# Half_Bridge_Driver.net
KiCad netlist of a schematic drawn in Altium Designer
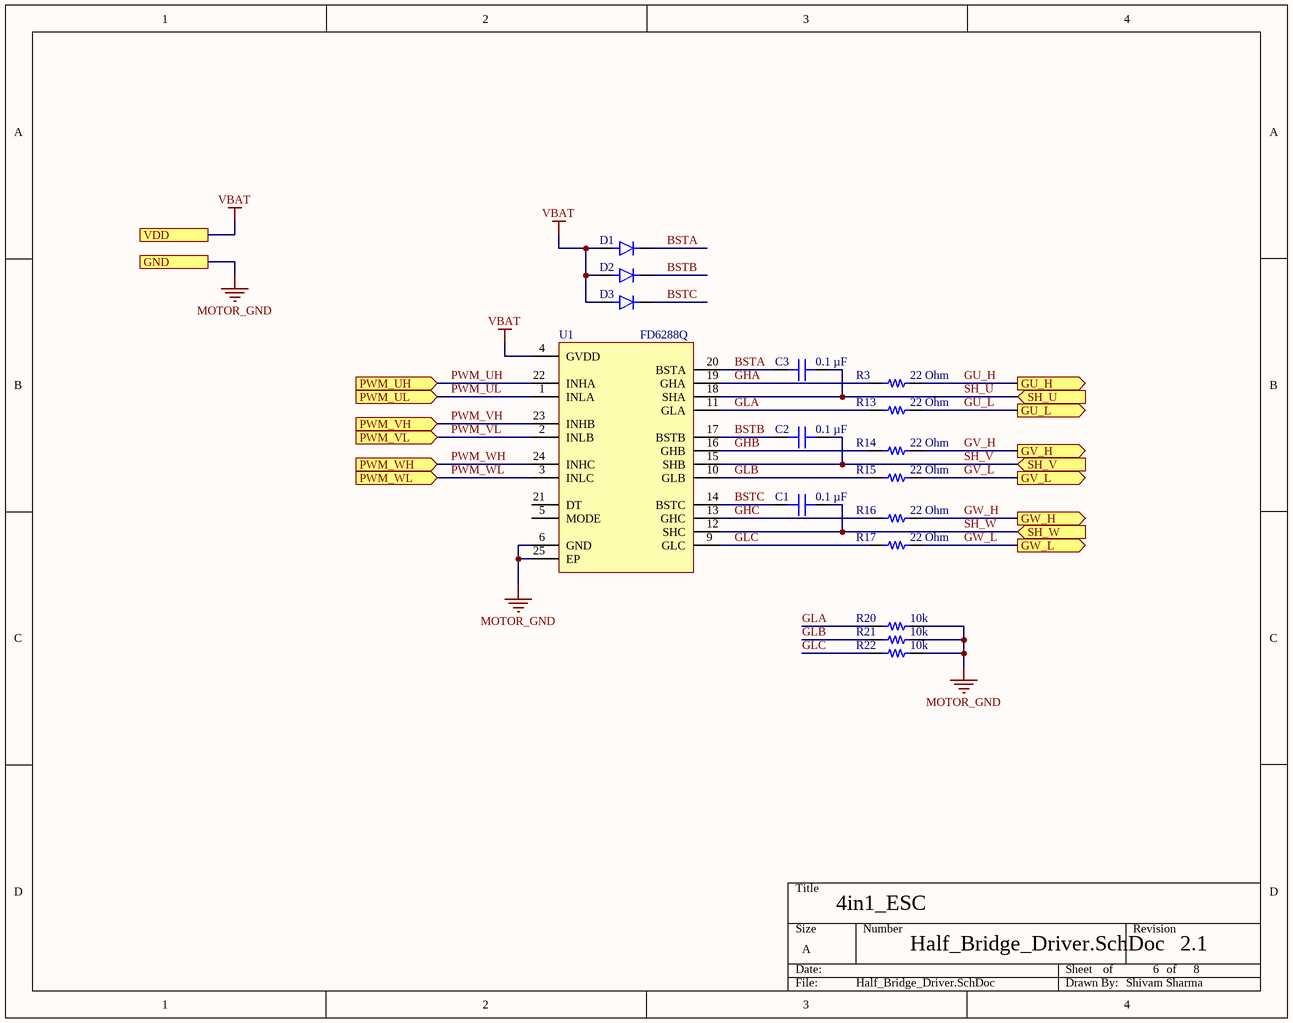
[diagram p0: Half_Bridge_Driver.SchDoc]

(export (version "E")
  (design (tool "Eeschema 10.0.6"))
  (components
    (comp (ref "C1")
      (value "0.1 µF")
      (footprint "CAP 0201_0603")
      (description "CAP CER 0.1UF 35V X5R 0201")
      (fields
        (field (name "PART NUMBER") "GRT033R6YA104KE01D")
        (field (name "MANUFACTURER") "Murata Electronics")
      )
      (libsource (lib "Celestial Altium Library - altium_library") (part "Capacitor"))
    )
    (comp (ref "C2")
      (value "0.1 µF")
      (footprint "CAP 0201_0603")
      (description "CAP CER 0.1UF 35V X5R 0201")
      (fields
        (field (name "PART NUMBER") "GRT033R6YA104KE01D")
        (field (name "MANUFACTURER") "Murata Electronics")
      )
      (libsource (lib "Celestial Altium Library - altium_library") (part "Capacitor"))
    )
    (comp (ref "C3")
      (value "0.1 µF")
      (footprint "CAP 0201_0603")
      (description "CAP CER 0.1UF 35V X5R 0201")
      (fields
        (field (name "PART NUMBER") "GRT033R6YA104KE01D")
        (field (name "MANUFACTURER") "Murata Electronics")
      )
      (libsource (lib "Celestial Altium Library - altium_library") (part "Capacitor"))
    )
    (comp (ref "D1")
      (value "Diode")
      (footprint "Diode DFN1608D-2 (SOD1608)")
      (description "DFN1608D-2 (SOD1608)")
      (fields (field (name "MANUFACTURER") "Cree") (field (name "MOUSER PART NUMBER") "941-CLV1LFKBC7673673"))
      (libsource (lib "IC") (part "Diode"))
    )
    (comp (ref "D2")
      (value "Diode")
      (footprint "Diode DFN1608D-2 (SOD1608)")
      (description "DFN1608D-2 (SOD1608)")
      (fields (field (name "MANUFACTURER") "Cree") (field (name "MOUSER PART NUMBER") "941-CLV1LFKBC7673673"))
      (libsource (lib "IC") (part "Diode"))
    )
    (comp (ref "D3")
      (value "Diode")
      (footprint "Diode DFN1608D-2 (SOD1608)")
      (description "DFN1608D-2 (SOD1608)")
      (fields (field (name "MANUFACTURER") "Cree") (field (name "MOUSER PART NUMBER") "941-CLV1LFKBC7673673"))
      (libsource (lib "IC") (part "Diode"))
    )
    (comp (ref "R3")
      (value "22 Ohm")
      (footprint "RES 0402_1005")
      (description "RES 14.3K OHM 1% 1/10W 0402")
      (fields
        (field (name "PART NUMBER") "RK73H1ETTP1432F")
        (field (name "MANUFACTURER") "KOA Speer Electronics, Inc.")
      )
      (libsource (lib "Celestial Altium Library - altium_library") (part "Resistor"))
    )
    (comp (ref "R13")
      (value "22 Ohm")
      (footprint "RES 0402_1005")
      (description "RES 14.3K OHM 1% 1/10W 0402")
      (fields
        (field (name "PART NUMBER") "RK73H1ETTP1432F")
        (field (name "MANUFACTURER") "KOA Speer Electronics, Inc.")
      )
      (libsource (lib "Celestial Altium Library - altium_library") (part "Resistor"))
    )
    (comp (ref "R14")
      (value "22 Ohm")
      (footprint "RES 0402_1005")
      (description "RES 14.3K OHM 1% 1/10W 0402")
      (fields
        (field (name "PART NUMBER") "RK73H1ETTP1432F")
        (field (name "MANUFACTURER") "KOA Speer Electronics, Inc.")
      )
      (libsource (lib "Celestial Altium Library - altium_library") (part "Resistor"))
    )
    (comp (ref "R15")
      (value "22 Ohm")
      (footprint "RES 0402_1005")
      (description "RES 14.3K OHM 1% 1/10W 0402")
      (fields
        (field (name "PART NUMBER") "RK73H1ETTP1432F")
        (field (name "MANUFACTURER") "KOA Speer Electronics, Inc.")
      )
      (libsource (lib "Celestial Altium Library - altium_library") (part "Resistor"))
    )
    (comp (ref "R16")
      (value "22 Ohm")
      (footprint "RES 0402_1005")
      (description "RES 14.3K OHM 1% 1/10W 0402")
      (fields
        (field (name "PART NUMBER") "RK73H1ETTP1432F")
        (field (name "MANUFACTURER") "KOA Speer Electronics, Inc.")
      )
      (libsource (lib "Celestial Altium Library - altium_library") (part "Resistor"))
    )
    (comp (ref "R17")
      (value "22 Ohm")
      (footprint "RES 0402_1005")
      (description "RES 14.3K OHM 1% 1/10W 0402")
      (fields
        (field (name "PART NUMBER") "RK73H1ETTP1432F")
        (field (name "MANUFACTURER") "KOA Speer Electronics, Inc.")
      )
      (libsource (lib "Celestial Altium Library - altium_library") (part "Resistor"))
    )
    (comp (ref "R20")
      (value "10k")
      (footprint "RES 0201_0603")
      (description "RES SMD 10K OHM 1% 1/20W 0201")
      (fields (field (name "PART NUMBER") "CRCW020110K0FKED") (field (name "MANUFACTURER") "Vishay Dale"))
      (libsource (lib "Celestial Altium Library - altium_library") (part "Resistor"))
    )
    (comp (ref "R21")
      (value "10k")
      (footprint "RES 0201_0603")
      (description "RES SMD 10K OHM 1% 1/20W 0201")
      (fields (field (name "PART NUMBER") "CRCW020110K0FKED") (field (name "MANUFACTURER") "Vishay Dale"))
      (libsource (lib "Celestial Altium Library - altium_library") (part "Resistor"))
    )
    (comp (ref "R22")
      (value "10k")
      (footprint "RES 0201_0603")
      (description "RES SMD 10K OHM 1% 1/20W 0201")
      (fields (field (name "PART NUMBER") "CRCW020110K0FKED") (field (name "MANUFACTURER") "Vishay Dale"))
      (libsource (lib "Celestial Altium Library - altium_library") (part "Resistor"))
    )
    (comp (ref "U1")
      (value "FD6288Q")
      (footprint "QFN50P400X400X100-25N")
      (description "3 Phase Gate Driver 1.5-2.2A")
      (fields (field (name "MF") "Texas Instruments") (field (name "MP") "UCC27282DRCR"))
      (libsource (lib "IC") (part "FD6288Q"))
    )
  )
  (nets
    (net (code "1") (name "/BSTA") (class "Default")
      (node (ref "C3") (pin "1") (pinfunction "1_1") (pintype "passive"))
      (node (ref "D1") (pin "1") (pinfunction "A_1") (pintype "passive"))
      (node (ref "U1") (pin "20") (pinfunction "BSTA_20") (pintype "passive"))
    )
    (net (code "2") (name "/BSTB") (class "Default")
      (node (ref "C2") (pin "1") (pinfunction "1_1") (pintype "passive"))
      (node (ref "D2") (pin "1") (pinfunction "A_1") (pintype "passive"))
      (node (ref "U1") (pin "17") (pinfunction "BSTB_17") (pintype "passive"))
    )
    (net (code "3") (name "/BSTC") (class "Default")
      (node (ref "C1") (pin "1") (pinfunction "1_1") (pintype "passive"))
      (node (ref "D3") (pin "1") (pinfunction "A_1") (pintype "passive"))
      (node (ref "U1") (pin "14") (pinfunction "BSTC_14") (pintype "passive"))
    )
    (net (code "4") (name "/GHA") (class "Default")
      (node (ref "R3") (pin "1") (pinfunction "1_1") (pintype "passive"))
      (node (ref "U1") (pin "19") (pinfunction "GHA_19") (pintype "passive"))
    )
    (net (code "5") (name "/GHB") (class "Default")
      (node (ref "R14") (pin "1") (pinfunction "1_1") (pintype "passive"))
      (node (ref "U1") (pin "16") (pinfunction "GHB_16") (pintype "passive"))
    )
    (net (code "6") (name "/GHC") (class "Default")
      (node (ref "R16") (pin "1") (pinfunction "1_1") (pintype "passive"))
      (node (ref "U1") (pin "13") (pinfunction "GHC_13") (pintype "passive"))
    )
    (net (code "7") (name "/GLA") (class "Default")
      (node (ref "R13") (pin "1") (pinfunction "1_1") (pintype "passive"))
      (node (ref "R20") (pin "1") (pinfunction "1_1") (pintype "passive"))
      (node (ref "U1") (pin "11") (pinfunction "GLA_11") (pintype "passive"))
    )
    (net (code "8") (name "/GLB") (class "Default")
      (node (ref "R15") (pin "1") (pinfunction "1_1") (pintype "passive"))
      (node (ref "R21") (pin "1") (pinfunction "1_1") (pintype "passive"))
      (node (ref "U1") (pin "10") (pinfunction "GLB_10") (pintype "passive"))
    )
    (net (code "9") (name "/GLC") (class "Default")
      (node (ref "R17") (pin "1") (pinfunction "1_1") (pintype "passive"))
      (node (ref "R22") (pin "1") (pinfunction "1_1") (pintype "passive"))
      (node (ref "U1") (pin "9") (pinfunction "GLC_9") (pintype "passive"))
    )
    (net (code "10") (name "/GU_H") (class "Default")
      (node (ref "R3") (pin "2") (pinfunction "2_2") (pintype "passive"))
    )
    (net (code "11") (name "/GU_L") (class "Default")
      (node (ref "R13") (pin "2") (pinfunction "2_2") (pintype "passive"))
    )
    (net (code "12") (name "/GV_H") (class "Default")
      (node (ref "R14") (pin "2") (pinfunction "2_2") (pintype "passive"))
    )
    (net (code "13") (name "/GV_L") (class "Default")
      (node (ref "R15") (pin "2") (pinfunction "2_2") (pintype "passive"))
    )
    (net (code "14") (name "/GW_H") (class "Default")
      (node (ref "R16") (pin "2") (pinfunction "2_2") (pintype "passive"))
    )
    (net (code "15") (name "/GW_L") (class "Default")
      (node (ref "R17") (pin "2") (pinfunction "2_2") (pintype "passive"))
    )
    (net (code "16") (name "/PWM_UH") (class "Default")
      (node (ref "U1") (pin "22") (pinfunction "INHA_22") (pintype "passive"))
    )
    (net (code "17") (name "/PWM_UL") (class "Default")
      (node (ref "U1") (pin "1") (pinfunction "INLA_1") (pintype "passive"))
    )
    (net (code "18") (name "/PWM_VH") (class "Default")
      (node (ref "U1") (pin "23") (pinfunction "INHB_23") (pintype "passive"))
    )
    (net (code "19") (name "/PWM_VL") (class "Default")
      (node (ref "U1") (pin "2") (pinfunction "INLB_2") (pintype "passive"))
    )
    (net (code "20") (name "/PWM_WH") (class "Default")
      (node (ref "U1") (pin "24") (pinfunction "INHC_24") (pintype "passive"))
    )
    (net (code "21") (name "/PWM_WL") (class "Default")
      (node (ref "U1") (pin "3") (pinfunction "INLC_3") (pintype "passive"))
    )
    (net (code "22") (name "/SH_U") (class "Default")
      (node (ref "C3") (pin "2") (pinfunction "2_2") (pintype "passive"))
      (node (ref "U1") (pin "18") (pinfunction "SHA_18") (pintype "passive"))
    )
    (net (code "23") (name "/SH_V") (class "Default")
      (node (ref "C2") (pin "2") (pinfunction "2_2") (pintype "passive"))
      (node (ref "U1") (pin "15") (pinfunction "SHB_15") (pintype "passive"))
    )
    (net (code "24") (name "/SH_W") (class "Default")
      (node (ref "C1") (pin "2") (pinfunction "2_2") (pintype "passive"))
      (node (ref "U1") (pin "12") (pinfunction "SHC_12") (pintype "passive"))
    )
    (net (code "25") (name "MOTOR_GND") (class "Default")
      (node (ref "R20") (pin "2") (pinfunction "2_2") (pintype "passive"))
      (node (ref "R21") (pin "2") (pinfunction "2_2") (pintype "passive"))
      (node (ref "R22") (pin "2") (pinfunction "2_2") (pintype "passive"))
      (node (ref "U1") (pin "25") (pinfunction "EP_25") (pintype "passive"))
      (node (ref "U1") (pin "6") (pinfunction "GND_6") (pintype "passive"))
    )
    (net (code "26") (name "VBAT") (class "Default")
      (node (ref "D1") (pin "2") (pinfunction "BLUE(C)_2") (pintype "passive"))
      (node (ref "D2") (pin "2") (pinfunction "BLUE(C)_2") (pintype "passive"))
      (node (ref "D3") (pin "2") (pinfunction "BLUE(C)_2") (pintype "passive"))
      (node (ref "U1") (pin "4") (pinfunction "GVDD_4") (pintype "passive"))
    )
    (net (code "27") (name "unconnected-(U1-DT-Pad21)") (class "Default")
      (node (ref "U1") (pin "21") (pinfunction "DT_21") (pintype "passive"))
    )
    (net (code "28") (name "unconnected-(U1-MODE-Pad5)") (class "Default")
      (node (ref "U1") (pin "5") (pinfunction "MODE_5") (pintype "passive"))
    )
  )
)
